# TPS61032-AAA.net
KiCad netlist of a schematic drawn in EAGLE
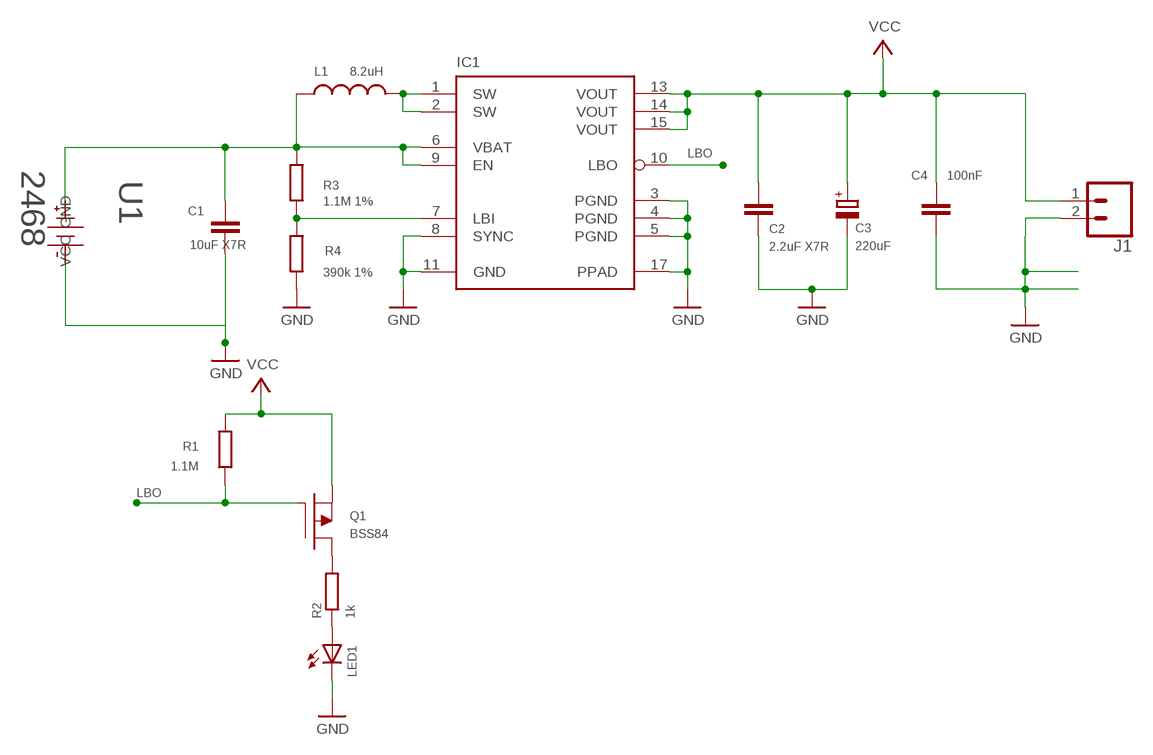
[diagram p0: schematic, sheet 1]

(export (version "E")
  (design (tool "Eeschema 10.0.6"))
  (components
    (comp (ref "C1")
      (value "10uF X7R")
      (footprint "eagle-import:CAPC2012X130N")
      (libsource (lib "eagle-import") (part "C0805"))
    )
    (comp (ref "C2")
      (value "2.2uF X7R")
      (footprint "eagle-import:CAPC2012X130N")
      (libsource (lib "eagle-import") (part "C0805"))
    )
    (comp (ref "C3")
      (value "220uF")
      (footprint "eagle-import:CAPMP3528X210N")
      (libsource (lib "eagle-import") (part "CPMLD-B"))
    )
    (comp (ref "C4")
      (value "100nF")
      (footprint "eagle-import:CAPC1608X55N")
      (libsource (lib "eagle-import") (part "C0603"))
    )
    (comp (ref "IC1")
      (value "TPS61032")
      (footprint "eagle-import:MO-153+PAD")
      (libsource (lib "eagle-import") (part "TPS61032"))
    )
    (comp (ref "J1")
      (value "CONN_02PTH4")
      (footprint "eagle-import:1X02_XTRA_BIG")
      (libsource (lib "eagle-import") (part "CONN_02PTH4"))
    )
    (comp (ref "L1")
      (value "8.2uH")
      (footprint "eagle-import:7443550820")
      (libsource (lib "eagle-import") (part "LWE-HCI-13MM"))
    )
    (comp (ref "LED1")
      (value "LED0603")
      (footprint "eagle-import:LEDC1608X60N")
      (libsource (lib "eagle-import") (part "LED0603"))
    )
    (comp (ref "Q1")
      (value "BSS84")
      (footprint "eagle-import:SOT95P240X110-3N")
      (libsource (lib "eagle-import") (part "PFET_SOT23"))
    )
    (comp (ref "R1")
      (value "1.1M")
      (footprint "eagle-import:RESC1508X63N")
      (libsource (lib "eagle-import") (part "R0603"))
    )
    (comp (ref "R2")
      (value "1k")
      (footprint "eagle-import:RESC1508X63N")
      (libsource (lib "eagle-import") (part "R0603"))
    )
    (comp (ref "R3")
      (value "1.1M 1%")
      (footprint "eagle-import:RESC1508X63N")
      (libsource (lib "eagle-import") (part "R0603"))
    )
    (comp (ref "R4")
      (value "390k 1%")
      (footprint "eagle-import:RESC1508X63N")
      (libsource (lib "eagle-import") (part "R0603"))
    )
    (comp (ref "U1")
      (value "2468")
      (footprint "eagle-import:BAT_HLDR_2468")
      (libsource (lib "eagle-import") (part "2468"))
    )
  )
  (nets
    (net (code "1") (name "/LBO") (class "Default")
      (node (ref "IC1") (pin "10") (pinfunction "LBO_10") (pintype "open_collector"))
      (node (ref "Q1") (pin "1") (pinfunction "GATE_1") (pintype "passive"))
      (node (ref "R1") (pin "1") (pinfunction "1_1") (pintype "passive"))
    )
    (net (code "2") (name "GND") (class "Default")
      (node (ref "C1") (pin "2") (pinfunction "2_2") (pintype "passive"))
      (node (ref "C2") (pin "2") (pinfunction "2_2") (pintype "passive"))
      (node (ref "C3") (pin "2") (pinfunction "-_2") (pintype "passive"))
      (node (ref "C4") (pin "2") (pinfunction "2_2") (pintype "passive"))
      (node (ref "IC1") (pin "11") (pinfunction "GND_11") (pintype "power_in"))
      (node (ref "IC1") (pin "17") (pinfunction "PPAD_17") (pintype "power_in"))
      (node (ref "IC1") (pin "3") (pinfunction "PGND_3") (pintype "power_in"))
      (node (ref "IC1") (pin "4") (pinfunction "PGND_4") (pintype "power_in"))
      (node (ref "IC1") (pin "5") (pinfunction "PGND_5") (pintype "power_in"))
      (node (ref "IC1") (pin "8") (pinfunction "SYNC_8") (pintype "input"))
      (node (ref "J1") (pin "2") (pinfunction "2_2") (pintype "passive"))
      (node (ref "LED1") (pin "1") (pinfunction "C_1") (pintype "passive"))
      (node (ref "R4") (pin "1") (pinfunction "1_1") (pintype "passive"))
      (node (ref "U1") (pin "GND") (pinfunction "GND_GND") (pintype "passive"))
    )
    (net (code "3") (name "Net-(IC1-EN)") (class "Default")
      (node (ref "C1") (pin "1") (pinfunction "1_1") (pintype "passive"))
      (node (ref "IC1") (pin "6") (pinfunction "VBAT_6") (pintype "power_in"))
      (node (ref "IC1") (pin "9") (pinfunction "EN_9") (pintype "input"))
      (node (ref "L1") (pin "1") (pinfunction "1_1") (pintype "bidirectional"))
      (node (ref "R3") (pin "2") (pinfunction "2_2") (pintype "passive"))
      (node (ref "U1") (pin "VCC") (pinfunction "VCC_VCC") (pintype "passive"))
    )
    (net (code "4") (name "Net-(IC1-LBI)") (class "Default")
      (node (ref "IC1") (pin "7") (pinfunction "LBI_7") (pintype "passive"))
      (node (ref "R3") (pin "1") (pinfunction "1_1") (pintype "passive"))
      (node (ref "R4") (pin "2") (pinfunction "2_2") (pintype "passive"))
    )
    (net (code "5") (name "Net-(IC1-SW-Pad1)") (class "Default")
      (node (ref "IC1") (pin "1") (pinfunction "SW_1") (pintype "passive"))
      (node (ref "IC1") (pin "2") (pinfunction "SW_2") (pintype "passive"))
      (node (ref "L1") (pin "2") (pinfunction "2_2") (pintype "bidirectional"))
    )
    (net (code "6") (name "Net-(LED1-A)") (class "Default")
      (node (ref "LED1") (pin "2") (pinfunction "A_2") (pintype "passive"))
      (node (ref "R2") (pin "1") (pinfunction "1_1") (pintype "passive"))
    )
    (net (code "7") (name "Net-(Q1-DRAIN)") (class "Default")
      (node (ref "Q1") (pin "3") (pinfunction "DRAIN_3") (pintype "passive"))
      (node (ref "R2") (pin "2") (pinfunction "2_2") (pintype "passive"))
    )
    (net (code "8") (name "VCC") (class "Default")
      (node (ref "C2") (pin "1") (pinfunction "1_1") (pintype "passive"))
      (node (ref "C3") (pin "1") (pinfunction "+_1") (pintype "passive"))
      (node (ref "C4") (pin "1") (pinfunction "1_1") (pintype "passive"))
      (node (ref "IC1") (pin "13") (pinfunction "VOUT_13") (pintype "passive"))
      (node (ref "IC1") (pin "14") (pinfunction "VOUT_14") (pintype "passive"))
      (node (ref "IC1") (pin "15") (pinfunction "VOUT_15") (pintype "passive"))
      (node (ref "J1") (pin "1") (pinfunction "1_1") (pintype "passive"))
      (node (ref "Q1") (pin "2") (pinfunction "SOURCE_2") (pintype "passive"))
      (node (ref "R1") (pin "2") (pinfunction "2_2") (pintype "passive"))
    )
  )
)
